# Relay.net
KiCad netlist of a schematic drawn in EAGLE
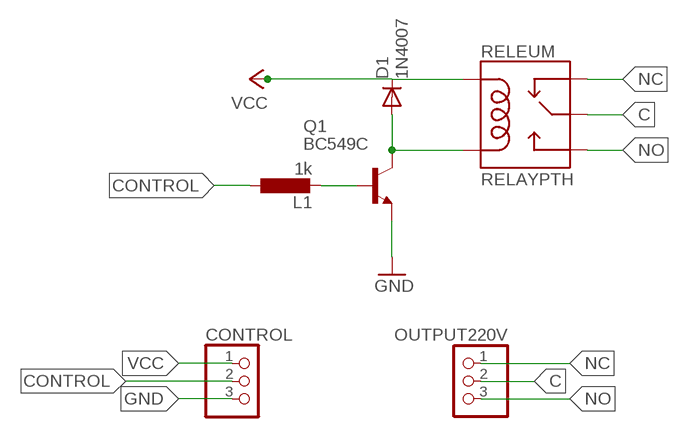
[diagram p0: schematic, sheet 1]

(export (version "E")
  (design (tool "Eeschema 10.0.6"))
  (components
    (comp (ref "CONTROL")
      (value "PINHD-1X3M")
      (footprint "eagle-import:1X03M")
      (libsource (lib "eagle-import") (part "PINHD-1X3M"))
    )
    (comp (ref "D1")
      (value "1N4007")
      (footprint "eagle-import:DO41-10")
      (libsource (lib "eagle-import") (part "1N4004"))
    )
    (comp (ref "L1")
      (value "1k")
      (footprint "eagle-import:0204_7")
      (libsource (lib "eagle-import") (part "L-EU0204/7"))
    )
    (comp (ref "OUTPUT220V")
      (value "PINHD-1X3M")
      (footprint "eagle-import:1X03M")
      (libsource (lib "eagle-import") (part "PINHD-1X3M"))
    )
    (comp (ref "Q1")
      (value "BC549C")
      (footprint "eagle-import:TO92-EBC")
      (libsource (lib "eagle-import") (part "BC549C"))
    )
    (comp (ref "RELEUM")
      (value "RELAYPTH")
      (footprint "eagle-import:SRD-05VDC-SL-C")
      (libsource (lib "eagle-import") (part "RELAYPTH"))
    )
  )
  (nets
    (net (code "1") (name "C") (class "Default")
      (node (ref "OUTPUT220V") (pin "2") (pinfunction "2_2") (pintype "passive"))
      (node (ref "RELEUM") (pin "SWCOMMON") (pinfunction "SWCOMMON_SWCOMMON") (pintype "bidirectional"))
    )
    (net (code "2") (name "CONTROL") (class "Default")
      (node (ref "CONTROL") (pin "2") (pinfunction "2_2") (pintype "passive"))
      (node (ref "L1") (pin "1") (pinfunction "1_1") (pintype "passive"))
    )
    (net (code "3") (name "GND") (class "Default")
      (node (ref "CONTROL") (pin "3") (pinfunction "3_3") (pintype "passive"))
      (node (ref "Q1") (pin "E") (pinfunction "E_E") (pintype "passive"))
    )
    (net (code "4") (name "NC") (class "Default")
      (node (ref "OUTPUT220V") (pin "1") (pinfunction "1_1") (pintype "passive"))
      (node (ref "RELEUM") (pin "SWCLOSED") (pinfunction "SWCLOSE_SWCLOSED") (pintype "bidirectional"))
    )
    (net (code "5") (name "NO") (class "Default")
      (node (ref "OUTPUT220V") (pin "3") (pinfunction "3_3") (pintype "passive"))
      (node (ref "RELEUM") (pin "SWOPEN") (pinfunction "SWOPEN_SWOPEN") (pintype "bidirectional"))
    )
    (net (code "6") (name "Net-(D1-PadA)") (class "Default")
      (node (ref "D1") (pin "A") (pinfunction "A_A") (pintype "passive"))
      (node (ref "Q1") (pin "C") (pinfunction "C_C") (pintype "passive"))
      (node (ref "RELEUM") (pin "COIL0") (pinfunction "COIL0_COIL0") (pintype "bidirectional"))
    )
    (net (code "7") (name "Net-(L1-Pad2)") (class "Default")
      (node (ref "L1") (pin "2") (pinfunction "2_2") (pintype "passive"))
      (node (ref "Q1") (pin "B") (pinfunction "B_B") (pintype "passive"))
    )
    (net (code "8") (name "VCC") (class "Default")
      (node (ref "CONTROL") (pin "1") (pinfunction "1_1") (pintype "passive"))
      (node (ref "D1") (pin "C") (pinfunction "C_C") (pintype "passive"))
      (node (ref "RELEUM") (pin "COIL1") (pinfunction "COIL1_COIL1") (pintype "bidirectional"))
    )
  )
)
